# UBX_NORA_B1_SCHEM_0001_NORA_B1_Module.net
KiCad netlist of a schematic drawn in Altium Designer
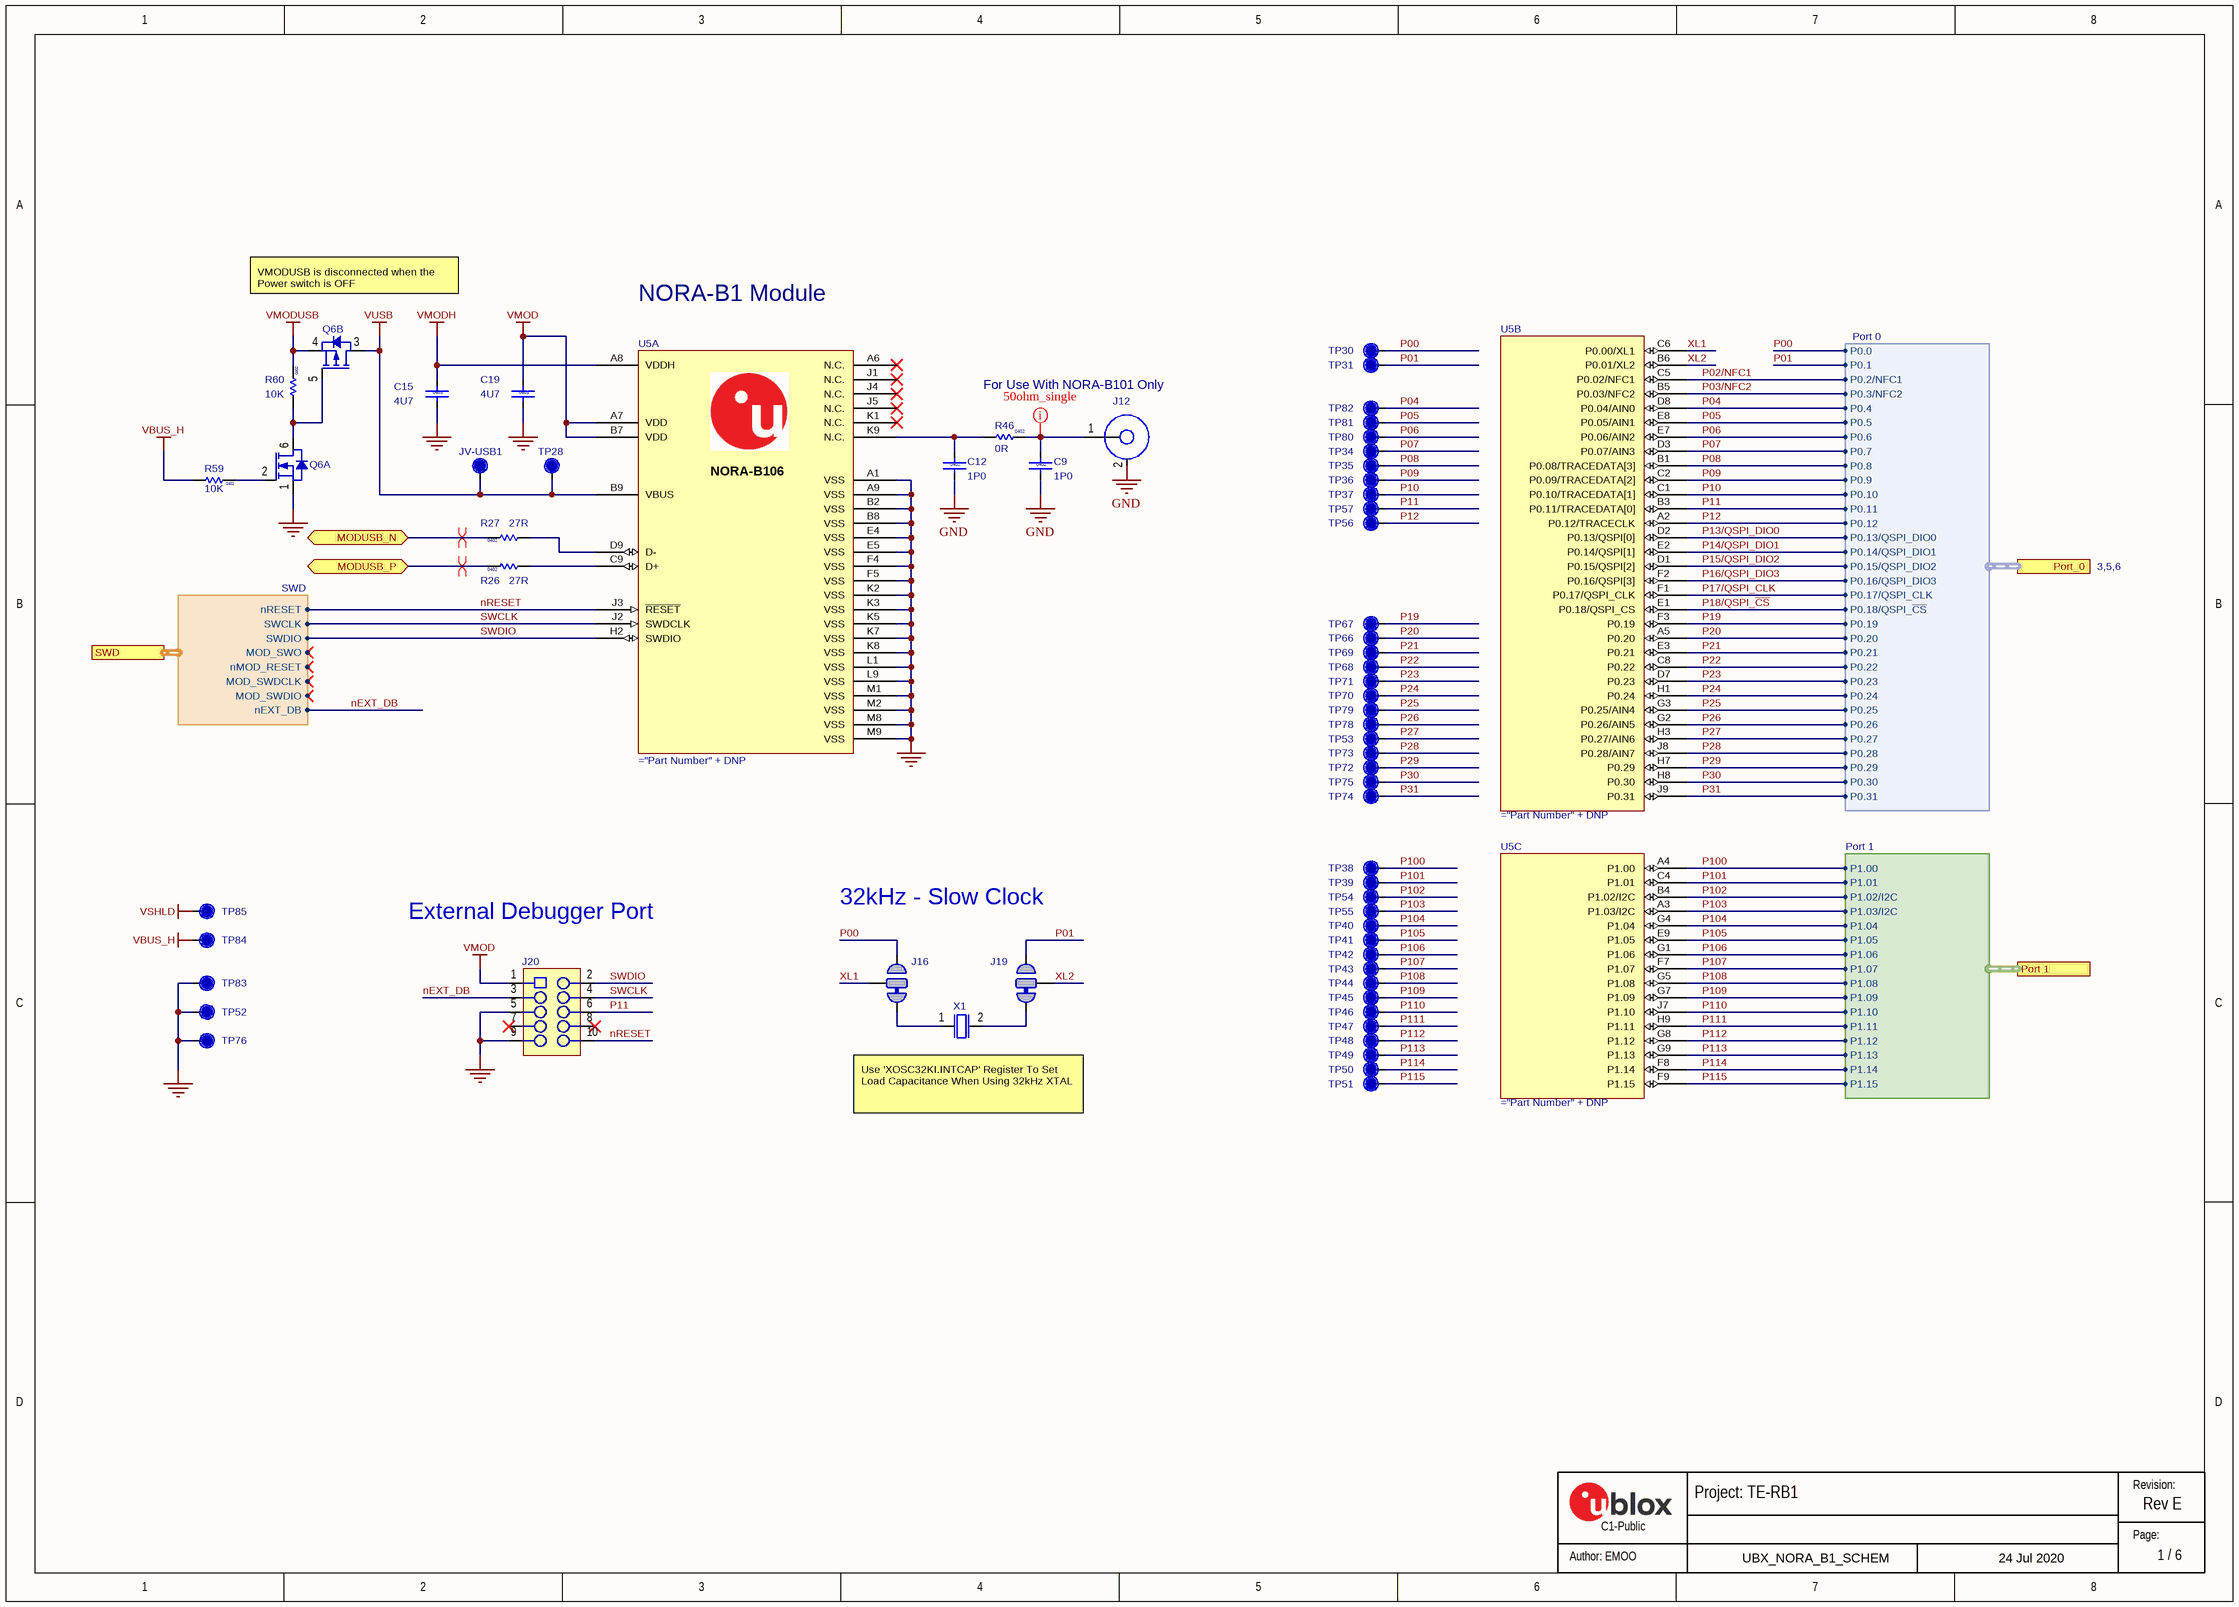
[diagram p0: UBX_NORA_B1_SCHEM_0001_NORA_B1_Module.SchDoc]

(export (version "E")
  (design (tool "Eeschema 10.0.6"))
  (components
    (comp (ref "C9")
      (value "1P0")
      (footprint "Cap 0402 HD")
      (description "CAP CER C0G 0402 1P0 +/-0.1P 50V")
      (fields
        (field (name "SIZE") "0402")
        (field (name "PART NUMBER") "UBXH01-0009002")
        (field (name "TOLERANCE") "+/-0.1P")
        (field (name "EDITOR") "massimo.vlacci")
        (field (name "RELEASED BY") "sandro.sestan")
      )
      (libsource (lib "UBX_Parts_DB_Lib") (part "Cap Chip"))
    )
    (comp (ref "C12")
      (value "1P0")
      (footprint "Cap 0402 HD")
      (description "CAP CER C0G 0402 1P0 +/-0.1P 50V")
      (fields
        (field (name "SIZE") "0402")
        (field (name "PART NUMBER") "UBXH01-0009002")
        (field (name "TOLERANCE") "+/-0.1P")
        (field (name "EDITOR") "massimo.vlacci")
        (field (name "RELEASED BY") "sandro.sestan")
      )
      (libsource (lib "UBX_Parts_DB_Lib") (part "Cap Chip"))
    )
    (comp (ref "C15")
      (value "4U7")
      (footprint "CAP 0603 HD")
      (description "CAP CER X5R 0603 4U7 10% 6.3V")
      (fields
        (field (name "SIZE") "0603")
        (field (name "PART NUMBER") "UBXH01-2002003")
        (field (name "TOLERANCE") "10%")
        (field (name "EDITOR") "philippe.largier")
        (field (name "RELEASED BY") "roland.rust")
      )
      (libsource (lib "UBX_Parts_DB_Lib") (part "Cap Chip"))
    )
    (comp (ref "C19")
      (value "4U7")
      (footprint "CAP 0603 HD")
      (description "CAP CER X5R 0603 4U7 10% 6.3V")
      (fields
        (field (name "SIZE") "0603")
        (field (name "PART NUMBER") "UBXH01-2002003")
        (field (name "TOLERANCE") "10%")
        (field (name "EDITOR") "philippe.largier")
        (field (name "RELEASED BY") "roland.rust")
      )
      (libsource (lib "UBX_Parts_DB_Lib") (part "Cap Chip"))
    )
    (comp (ref "J12")
      (value "UBXH04-0000657")
      (footprint "U.FL_3Pin")
      (description "CONN U.FL STRAIGHT RECEPTACLE")
      (fields
        (field (name "MANUFACTURER") "Hirose")
        (field (name "EDITOR") "cam.nichols")
        (field (name "RELEASED BY") "eric.moog")
      )
      (libsource (lib "UBX_Parts_DB_Lib") (part "CON_Coax_2Pin"))
    )
    (comp (ref "J16")
      (value "UBXH00-0000083")
      (footprint "Solderbridge-Option")
      (description "SOLDERBRIDGE-OPTION")
      (fields (field (name "EDITOR") "aneeb.sohail"))
      (libsource (lib "") (part "Solderbridge-Option_1"))
    )
    (comp (ref "J19")
      (value "UBXH00-0000083")
      (footprint "Solderbridge-Option")
      (description "SOLDERBRIDGE-OPTION")
      (fields (field (name "EDITOR") "aneeb.sohail"))
      (libsource (lib "UBX_Parts_DB_Lib") (part "Solderbridge-Option"))
    )
    (comp (ref "J20")
      (value "UBXH04-0000194")
      (footprint "FTSH-105-01-F-DV-K")
      (description "2-ROW SMD-PCB CONN 50MIL GRID 10 -PIN 0.41MM SQUARE 4.0MM KEYED")
      (fields
        (field (name "MANUFACTURER") "Samtec")
        (field (name "EDITOR") "par.hakansson")
        (field (name "RELEASED BY") "adam.johansson")
      )
      (libsource (lib "UBX_Parts_DB_Lib") (part "CON-10Pin_2Row"))
    )
    (comp (ref "JV-USB1")
      (value "TP")
      (footprint "TP10R_NO_SILK")
      (description "TESTPOINT 1MM CIRCULAR NO SILKSCREEN")
      (fields (field (name "PART NUMBER") "UBXH00-0000096") (field (name "EDITOR") "eric.moog"))
      (libsource (lib "UBX_Parts_DB_Lib") (part "TP_R"))
    )
    (comp (ref "Q6")
      (value "UBXH20-0000084")
      (footprint "SOT-563")
      (description "SMALL SIGNAL COMPLEMENTARY W/ ESD PROTECTION MOSFET SOT-563-6 PACKAGE")
      (fields
        (field (name "MANUFACTURER") "ON Semiconductor")
        (field (name "EDITOR") "pierpaolo.arban")
        (field (name "RELEASED BY") "matej.budin")
      )
      (libsource (lib "UBX_Parts_DB_Lib") (part "MOSFET-N-P_Pair"))
    )
    (comp (ref "R26")
      (value "27R")
      (footprint "RES 0402 HD")
      (description "RES THICK FILM CHIP 0402 27R 5% 100mW")
      (fields
        (field (name "SIZE") "0402")
        (field (name "PART NUMBER") "UBXH18-0008011")
        (field (name "TOLERANCE") "5%")
        (field (name "EDITOR") "roland.rust")
        (field (name "RELEASED BY") "roland.rust")
      )
      (libsource (lib "UBX_Parts_DB_Lib") (part "Res sm"))
    )
    (comp (ref "R27")
      (value "27R")
      (footprint "RES 0402 HD")
      (description "RES THICK FILM CHIP 0402 27R 5% 100mW")
      (fields
        (field (name "SIZE") "0402")
        (field (name "PART NUMBER") "UBXH18-0008011")
        (field (name "TOLERANCE") "5%")
        (field (name "EDITOR") "roland.rust")
        (field (name "RELEASED BY") "roland.rust")
      )
      (libsource (lib "UBX_Parts_DB_Lib") (part "Res sm"))
    )
    (comp (ref "R46")
      (value "0R")
      (footprint "RES 0402 HD")
      (description "RES THICK FILM CHIP 0402 0R 0 100mW")
      (fields
        (field (name "SIZE") "0402")
        (field (name "PART NUMBER") "UBXH18-0003002")
        (field (name "TOLERANCE") "0")
        (field (name "EDITOR") "charlotte.biber")
        (field (name "RELEASED BY") "peter.mueller")
      )
      (libsource (lib "UBX_Parts_DB_Lib") (part "Res sm"))
    )
    (comp (ref "R59")
      (value "10K")
      (footprint "RES 0402 HD")
      (description "RES THICK FILM CHIP 0402 10K 1% 63mW")
      (fields
        (field (name "SIZE") "0402")
        (field (name "PART NUMBER") "UBXH18-0000065")
        (field (name "TOLERANCE") "1%")
        (field (name "EDITOR") "erian.bezhani")
        (field (name "RELEASED BY") "massimo.vlacci")
      )
      (libsource (lib "UBX_Parts_DB_Lib") (part "Res sm"))
    )
    (comp (ref "R60")
      (value "10K")
      (footprint "RES 0402 HD")
      (description "RES THICK FILM CHIP 0402 10K 1% 63mW")
      (fields
        (field (name "SIZE") "0402")
        (field (name "PART NUMBER") "UBXH18-0000065")
        (field (name "TOLERANCE") "1%")
        (field (name "EDITOR") "erian.bezhani")
        (field (name "RELEASED BY") "massimo.vlacci")
      )
      (libsource (lib "UBX_Parts_DB_Lib") (part "Res sm"))
    )
    (comp (ref "TP28")
      (value "TP")
      (footprint "TP10R_NO_SILK")
      (description "TESTPOINT 1MM CIRCULAR NO SILKSCREEN")
      (fields (field (name "PART NUMBER") "UBXH00-0000096") (field (name "EDITOR") "eric.moog"))
      (libsource (lib "UBX_Parts_DB_Lib") (part "TP_R"))
    )
    (comp (ref "TP30")
      (value "TP")
      (footprint "TP10R_NO_SILK")
      (description "TESTPOINT 1MM CIRCULAR NO SILKSCREEN")
      (fields (field (name "PART NUMBER") "UBXH00-0000096") (field (name "EDITOR") "eric.moog"))
      (libsource (lib "UBX_Parts_DB_Lib") (part "TP_R"))
    )
    (comp (ref "TP31")
      (value "TP")
      (footprint "TP10R_NO_SILK")
      (description "TESTPOINT 1MM CIRCULAR NO SILKSCREEN")
      (fields (field (name "PART NUMBER") "UBXH00-0000096") (field (name "EDITOR") "eric.moog"))
      (libsource (lib "UBX_Parts_DB_Lib") (part "TP_R"))
    )
    (comp (ref "TP34")
      (value "TP")
      (footprint "TP10R_NO_SILK")
      (description "TESTPOINT 1MM CIRCULAR NO SILKSCREEN")
      (fields (field (name "PART NUMBER") "UBXH00-0000096") (field (name "EDITOR") "eric.moog"))
      (libsource (lib "UBX_Parts_DB_Lib") (part "TP_R"))
    )
    (comp (ref "TP35")
      (value "TP")
      (footprint "TP10R_NO_SILK")
      (description "TESTPOINT 1MM CIRCULAR NO SILKSCREEN")
      (fields (field (name "PART NUMBER") "UBXH00-0000096") (field (name "EDITOR") "eric.moog"))
      (libsource (lib "UBX_Parts_DB_Lib") (part "TP_R"))
    )
    (comp (ref "TP36")
      (value "TP")
      (footprint "TP10R_NO_SILK")
      (description "TESTPOINT 1MM CIRCULAR NO SILKSCREEN")
      (fields (field (name "PART NUMBER") "UBXH00-0000096") (field (name "EDITOR") "eric.moog"))
      (libsource (lib "UBX_Parts_DB_Lib") (part "TP_R"))
    )
    (comp (ref "TP37")
      (value "TP")
      (footprint "TP10R_NO_SILK")
      (description "TESTPOINT 1MM CIRCULAR NO SILKSCREEN")
      (fields (field (name "PART NUMBER") "UBXH00-0000096") (field (name "EDITOR") "eric.moog"))
      (libsource (lib "UBX_Parts_DB_Lib") (part "TP_R"))
    )
    (comp (ref "TP38")
      (value "TP")
      (footprint "TP10R_NO_SILK")
      (description "TESTPOINT 1MM CIRCULAR NO SILKSCREEN")
      (fields (field (name "PART NUMBER") "UBXH00-0000096") (field (name "EDITOR") "eric.moog"))
      (libsource (lib "UBX_Parts_DB_Lib") (part "TP_R"))
    )
    (comp (ref "TP39")
      (value "TP")
      (footprint "TP10R_NO_SILK")
      (description "TESTPOINT 1MM CIRCULAR NO SILKSCREEN")
      (fields (field (name "PART NUMBER") "UBXH00-0000096") (field (name "EDITOR") "eric.moog"))
      (libsource (lib "UBX_Parts_DB_Lib") (part "TP_R"))
    )
    (comp (ref "TP40")
      (value "TP")
      (footprint "TP10R_NO_SILK")
      (description "TESTPOINT 1MM CIRCULAR NO SILKSCREEN")
      (fields (field (name "PART NUMBER") "UBXH00-0000096") (field (name "EDITOR") "eric.moog"))
      (libsource (lib "UBX_Parts_DB_Lib") (part "TP_R"))
    )
    (comp (ref "TP41")
      (value "TP")
      (footprint "TP10R_NO_SILK")
      (description "TESTPOINT 1MM CIRCULAR NO SILKSCREEN")
      (fields (field (name "PART NUMBER") "UBXH00-0000096") (field (name "EDITOR") "eric.moog"))
      (libsource (lib "UBX_Parts_DB_Lib") (part "TP_R"))
    )
    (comp (ref "TP42")
      (value "TP")
      (footprint "TP10R_NO_SILK")
      (description "TESTPOINT 1MM CIRCULAR NO SILKSCREEN")
      (fields (field (name "PART NUMBER") "UBXH00-0000096") (field (name "EDITOR") "eric.moog"))
      (libsource (lib "UBX_Parts_DB_Lib") (part "TP_R"))
    )
    (comp (ref "TP43")
      (value "TP")
      (footprint "TP10R_NO_SILK")
      (description "TESTPOINT 1MM CIRCULAR NO SILKSCREEN")
      (fields (field (name "PART NUMBER") "UBXH00-0000096") (field (name "EDITOR") "eric.moog"))
      (libsource (lib "UBX_Parts_DB_Lib") (part "TP_R"))
    )
    (comp (ref "TP44")
      (value "TP")
      (footprint "TP10R_NO_SILK")
      (description "TESTPOINT 1MM CIRCULAR NO SILKSCREEN")
      (fields (field (name "PART NUMBER") "UBXH00-0000096") (field (name "EDITOR") "eric.moog"))
      (libsource (lib "UBX_Parts_DB_Lib") (part "TP_R"))
    )
    (comp (ref "TP45")
      (value "TP")
      (footprint "TP10R_NO_SILK")
      (description "TESTPOINT 1MM CIRCULAR NO SILKSCREEN")
      (fields (field (name "PART NUMBER") "UBXH00-0000096") (field (name "EDITOR") "eric.moog"))
      (libsource (lib "UBX_Parts_DB_Lib") (part "TP_R"))
    )
    (comp (ref "TP46")
      (value "TP")
      (footprint "TP10R_NO_SILK")
      (description "TESTPOINT 1MM CIRCULAR NO SILKSCREEN")
      (fields (field (name "PART NUMBER") "UBXH00-0000096") (field (name "EDITOR") "eric.moog"))
      (libsource (lib "UBX_Parts_DB_Lib") (part "TP_R"))
    )
    (comp (ref "TP47")
      (value "TP")
      (footprint "TP10R_NO_SILK")
      (description "TESTPOINT 1MM CIRCULAR NO SILKSCREEN")
      (fields (field (name "PART NUMBER") "UBXH00-0000096") (field (name "EDITOR") "eric.moog"))
      (libsource (lib "UBX_Parts_DB_Lib") (part "TP_R"))
    )
    (comp (ref "TP48")
      (value "TP")
      (footprint "TP10R_NO_SILK")
      (description "TESTPOINT 1MM CIRCULAR NO SILKSCREEN")
      (fields (field (name "PART NUMBER") "UBXH00-0000096") (field (name "EDITOR") "eric.moog"))
      (libsource (lib "UBX_Parts_DB_Lib") (part "TP_R"))
    )
    (comp (ref "TP49")
      (value "TP")
      (footprint "TP10R_NO_SILK")
      (description "TESTPOINT 1MM CIRCULAR NO SILKSCREEN")
      (fields (field (name "PART NUMBER") "UBXH00-0000096") (field (name "EDITOR") "eric.moog"))
      (libsource (lib "UBX_Parts_DB_Lib") (part "TP_R"))
    )
    (comp (ref "TP50")
      (value "TP")
      (footprint "TP10R_NO_SILK")
      (description "TESTPOINT 1MM CIRCULAR NO SILKSCREEN")
      (fields (field (name "PART NUMBER") "UBXH00-0000096") (field (name "EDITOR") "eric.moog"))
      (libsource (lib "UBX_Parts_DB_Lib") (part "TP_R"))
    )
    (comp (ref "TP51")
      (value "TP")
      (footprint "TP10R_NO_SILK")
      (description "TESTPOINT 1MM CIRCULAR NO SILKSCREEN")
      (fields (field (name "PART NUMBER") "UBXH00-0000096") (field (name "EDITOR") "eric.moog"))
      (libsource (lib "UBX_Parts_DB_Lib") (part "TP_R"))
    )
    (comp (ref "TP52")
      (value "TP")
      (footprint "TP10R_NO_SILK")
      (description "TESTPOINT 1MM CIRCULAR NO SILKSCREEN")
      (fields (field (name "PART NUMBER") "UBXH00-0000096") (field (name "EDITOR") "eric.moog"))
      (libsource (lib "UBX_Parts_DB_Lib") (part "TP_R"))
    )
    (comp (ref "TP53")
      (value "TP")
      (footprint "TP10R_NO_SILK")
      (description "TESTPOINT 1MM CIRCULAR NO SILKSCREEN")
      (fields (field (name "PART NUMBER") "UBXH00-0000096") (field (name "EDITOR") "eric.moog"))
      (libsource (lib "UBX_Parts_DB_Lib") (part "TP_R"))
    )
    (comp (ref "TP54")
      (value "TP")
      (footprint "TP10R_NO_SILK")
      (description "TESTPOINT 1MM CIRCULAR NO SILKSCREEN")
      (fields (field (name "PART NUMBER") "UBXH00-0000096") (field (name "EDITOR") "eric.moog"))
      (libsource (lib "UBX_Parts_DB_Lib") (part "TP_R"))
    )
    (comp (ref "TP55")
      (value "TP")
      (footprint "TP10R_NO_SILK")
      (description "TESTPOINT 1MM CIRCULAR NO SILKSCREEN")
      (fields (field (name "PART NUMBER") "UBXH00-0000096") (field (name "EDITOR") "eric.moog"))
      (libsource (lib "UBX_Parts_DB_Lib") (part "TP_R"))
    )
    (comp (ref "TP56")
      (value "TP")
      (footprint "TP10R_NO_SILK")
      (description "TESTPOINT 1MM CIRCULAR NO SILKSCREEN")
      (fields (field (name "PART NUMBER") "UBXH00-0000096") (field (name "EDITOR") "eric.moog"))
      (libsource (lib "UBX_Parts_DB_Lib") (part "TP_R"))
    )
    (comp (ref "TP57")
      (value "TP")
      (footprint "TP10R_NO_SILK")
      (description "TESTPOINT 1MM CIRCULAR NO SILKSCREEN")
      (fields (field (name "PART NUMBER") "UBXH00-0000096") (field (name "EDITOR") "eric.moog"))
      (libsource (lib "UBX_Parts_DB_Lib") (part "TP_R"))
    )
    (comp (ref "TP66")
      (value "TP")
      (footprint "TP10R_NO_SILK")
      (description "TESTPOINT 1MM CIRCULAR NO SILKSCREEN")
      (fields (field (name "PART NUMBER") "UBXH00-0000096") (field (name "EDITOR") "eric.moog"))
      (libsource (lib "UBX_Parts_DB_Lib") (part "TP_R"))
    )
    (comp (ref "TP67")
      (value "TP")
      (footprint "TP10R_NO_SILK")
      (description "TESTPOINT 1MM CIRCULAR NO SILKSCREEN")
      (fields (field (name "PART NUMBER") "UBXH00-0000096") (field (name "EDITOR") "eric.moog"))
      (libsource (lib "UBX_Parts_DB_Lib") (part "TP_R"))
    )
    (comp (ref "TP68")
      (value "TP")
      (footprint "TP10R_NO_SILK")
      (description "TESTPOINT 1MM CIRCULAR NO SILKSCREEN")
      (fields (field (name "PART NUMBER") "UBXH00-0000096") (field (name "EDITOR") "eric.moog"))
      (libsource (lib "UBX_Parts_DB_Lib") (part "TP_R"))
    )
    (comp (ref "TP69")
      (value "TP")
      (footprint "TP10R_NO_SILK")
      (description "TESTPOINT 1MM CIRCULAR NO SILKSCREEN")
      (fields (field (name "PART NUMBER") "UBXH00-0000096") (field (name "EDITOR") "eric.moog"))
      (libsource (lib "UBX_Parts_DB_Lib") (part "TP_R"))
    )
    (comp (ref "TP70")
      (value "TP")
      (footprint "TP10R_NO_SILK")
      (description "TESTPOINT 1MM CIRCULAR NO SILKSCREEN")
      (fields (field (name "PART NUMBER") "UBXH00-0000096") (field (name "EDITOR") "eric.moog"))
      (libsource (lib "UBX_Parts_DB_Lib") (part "TP_R"))
    )
    (comp (ref "TP71")
      (value "TP")
      (footprint "TP10R_NO_SILK")
      (description "TESTPOINT 1MM CIRCULAR NO SILKSCREEN")
      (fields (field (name "PART NUMBER") "UBXH00-0000096") (field (name "EDITOR") "eric.moog"))
      (libsource (lib "UBX_Parts_DB_Lib") (part "TP_R"))
    )
    (comp (ref "TP72")
      (value "TP")
      (footprint "TP10R_NO_SILK")
      (description "TESTPOINT 1MM CIRCULAR NO SILKSCREEN")
      (fields (field (name "PART NUMBER") "UBXH00-0000096") (field (name "EDITOR") "eric.moog"))
      (libsource (lib "UBX_Parts_DB_Lib") (part "TP_R"))
    )
    (comp (ref "TP73")
      (value "TP")
      (footprint "TP10R_NO_SILK")
      (description "TESTPOINT 1MM CIRCULAR NO SILKSCREEN")
      (fields (field (name "PART NUMBER") "UBXH00-0000096") (field (name "EDITOR") "eric.moog"))
      (libsource (lib "UBX_Parts_DB_Lib") (part "TP_R"))
    )
    (comp (ref "TP74")
      (value "TP")
      (footprint "TP10R_NO_SILK")
      (description "TESTPOINT 1MM CIRCULAR NO SILKSCREEN")
      (fields (field (name "PART NUMBER") "UBXH00-0000096") (field (name "EDITOR") "eric.moog"))
      (libsource (lib "UBX_Parts_DB_Lib") (part "TP_R"))
    )
    (comp (ref "TP75")
      (value "TP")
      (footprint "TP10R_NO_SILK")
      (description "TESTPOINT 1MM CIRCULAR NO SILKSCREEN")
      (fields (field (name "PART NUMBER") "UBXH00-0000096") (field (name "EDITOR") "eric.moog"))
      (libsource (lib "UBX_Parts_DB_Lib") (part "TP_R"))
    )
    (comp (ref "TP76")
      (value "TP")
      (footprint "TP10R_NO_SILK")
      (description "TESTPOINT 1MM CIRCULAR NO SILKSCREEN")
      (fields (field (name "PART NUMBER") "UBXH00-0000096") (field (name "EDITOR") "eric.moog"))
      (libsource (lib "UBX_Parts_DB_Lib") (part "TP_R"))
    )
    (comp (ref "TP78")
      (value "TP")
      (footprint "TP10R_NO_SILK")
      (description "TESTPOINT 1MM CIRCULAR NO SILKSCREEN")
      (fields (field (name "PART NUMBER") "UBXH00-0000096") (field (name "EDITOR") "eric.moog"))
      (libsource (lib "UBX_Parts_DB_Lib") (part "TP_R"))
    )
    (comp (ref "TP79")
      (value "TP")
      (footprint "TP10R_NO_SILK")
      (description "TESTPOINT 1MM CIRCULAR NO SILKSCREEN")
      (fields (field (name "PART NUMBER") "UBXH00-0000096") (field (name "EDITOR") "eric.moog"))
      (libsource (lib "UBX_Parts_DB_Lib") (part "TP_R"))
    )
    (comp (ref "TP80")
      (value "TP")
      (footprint "TP10R_NO_SILK")
      (description "TESTPOINT 1MM CIRCULAR NO SILKSCREEN")
      (fields (field (name "PART NUMBER") "UBXH00-0000096") (field (name "EDITOR") "eric.moog"))
      (libsource (lib "UBX_Parts_DB_Lib") (part "TP_R"))
    )
    (comp (ref "TP81")
      (value "TP")
      (footprint "TP10R_NO_SILK")
      (description "TESTPOINT 1MM CIRCULAR NO SILKSCREEN")
      (fields (field (name "PART NUMBER") "UBXH00-0000096") (field (name "EDITOR") "eric.moog"))
      (libsource (lib "UBX_Parts_DB_Lib") (part "TP_R"))
    )
    (comp (ref "TP82")
      (value "TP")
      (footprint "TP10R_NO_SILK")
      (description "TESTPOINT 1MM CIRCULAR NO SILKSCREEN")
      (fields (field (name "PART NUMBER") "UBXH00-0000096") (field (name "EDITOR") "eric.moog"))
      (libsource (lib "UBX_Parts_DB_Lib") (part "TP_R"))
    )
    (comp (ref "TP83")
      (value "TP")
      (footprint "TP10R_NO_SILK")
      (description "TESTPOINT 1MM CIRCULAR NO SILKSCREEN")
      (fields (field (name "PART NUMBER") "UBXH00-0000096") (field (name "EDITOR") "eric.moog"))
      (libsource (lib "UBX_Parts_DB_Lib") (part "TP_R"))
    )
    (comp (ref "TP84")
      (value "TP")
      (footprint "TP10R_NO_SILK")
      (description "TESTPOINT 1MM CIRCULAR NO SILKSCREEN")
      (fields (field (name "PART NUMBER") "UBXH00-0000096") (field (name "EDITOR") "eric.moog"))
      (libsource (lib "UBX_Parts_DB_Lib") (part "TP_R"))
    )
    (comp (ref "TP85")
      (value "TP")
      (footprint "TP10R_NO_SILK")
      (description "TESTPOINT 1MM CIRCULAR NO SILKSCREEN")
      (fields (field (name "PART NUMBER") "UBXH00-0000096") (field (name "EDITOR") "eric.moog"))
      (libsource (lib "UBX_Parts_DB_Lib") (part "TP_R"))
    )
    (comp (ref "U5")
      (value "UBXH14-0000700")
      (footprint "NORA-B106")
      (description "SHORT RANGE BLE AND 802.15.4 MODULE U-BLOX NORA-B106 5.5V 10mA")
      (fields
        (field (name "MANUFACTURER") "u-blox")
        (field (name "VOLTAGE") "5.5V")
        (field (name "EDITOR") "eric.moog")
      )
      (libsource (lib "UBX_Parts_DB_Lib") (part "NORA-B106"))
    )
    (comp (ref "X1")
      (value "UBXH21-0000123")
      (footprint "XTAL_3215")
      (description "CRYSTAL CL=6PF 3.2 X 1.5 MM 32.768KHZ 20PPM")
      (fields
        (field (name "TOLERANCE") "20PPM")
        (field (name "MANUFACTURER") "ABRACON")
        (field (name "EDITOR") "martin.grasse")
      )
      (libsource (lib "UBX_Parts_DB_Lib") (part "XTAL_2Pin"))
    )
  )
  (nets
    (net (code "5") (name "/MODUSB_N") (class "Default")
      (node (ref "R27") (pin "2") (pinfunction "2_2") (pintype "passive"))
    )
    (net (code "6") (name "/MODUSB_P") (class "Default")
      (node (ref "R26") (pin "2") (pinfunction "2_2") (pintype "passive"))
    )
    (net (code "7") (name "/P00") (class "Default")
      (node (ref "J16") (pin "3") (pinfunction "3_3") (pintype "passive"))
      (node (ref "TP30") (pin "1") (pintype "passive"))
    )
    (net (code "8") (name "/P01") (class "Default")
      (node (ref "J19") (pin "3") (pinfunction "3_3") (pintype "passive"))
      (node (ref "TP31") (pin "1") (pintype "passive"))
    )
    (net (code "9") (name "/P02{slash}NFC1") (class "Default")
      (node (ref "U5") (pin "C5") (pinfunction "P0.02/NFC1_C5") (pintype "bidirectional"))
    )
    (net (code "10") (name "/P03{slash}NFC2") (class "Default")
      (node (ref "U5") (pin "B5") (pinfunction "P0.03/NFC2_B5") (pintype "bidirectional"))
    )
    (net (code "11") (name "/P04") (class "Default")
      (node (ref "TP82") (pin "1") (pintype "passive"))
      (node (ref "U5") (pin "D8") (pinfunction "P0.04/AIN0_D8") (pintype "bidirectional"))
    )
    (net (code "12") (name "/P05") (class "Default")
      (node (ref "TP81") (pin "1") (pintype "passive"))
      (node (ref "U5") (pin "E8") (pinfunction "P0.05/AIN1_E8") (pintype "bidirectional"))
    )
    (net (code "13") (name "/P06") (class "Default")
      (node (ref "TP80") (pin "1") (pintype "passive"))
      (node (ref "U5") (pin "E7") (pinfunction "P0.06/AIN2_E7") (pintype "bidirectional"))
    )
    (net (code "14") (name "/P07") (class "Default")
      (node (ref "TP34") (pin "1") (pintype "passive"))
      (node (ref "U5") (pin "D3") (pinfunction "P0.07/AIN3_D3") (pintype "bidirectional"))
    )
    (net (code "15") (name "/P08") (class "Default")
      (node (ref "TP35") (pin "1") (pintype "passive"))
      (node (ref "U5") (pin "B1") (pinfunction "P0.08/TRACEDATA[3]_B1") (pintype "bidirectional"))
    )
    (net (code "16") (name "/P09") (class "Default")
      (node (ref "TP36") (pin "1") (pintype "passive"))
      (node (ref "U5") (pin "C2") (pinfunction "P0.09/TRACEDATA[2]_C2") (pintype "bidirectional"))
    )
    (net (code "17") (name "/P10") (class "Default")
      (node (ref "TP37") (pin "1") (pintype "passive"))
      (node (ref "U5") (pin "C1") (pinfunction "P0.10/TRACEDATA[1]_C1") (pintype "bidirectional"))
    )
    (net (code "18") (name "/P11") (class "Default")
      (node (ref "J20") (pin "6") (pintype "passive"))
      (node (ref "TP57") (pin "1") (pintype "passive"))
      (node (ref "U5") (pin "B3") (pinfunction "P0.11/TRACEDATA[0]_B3") (pintype "bidirectional"))
    )
    (net (code "19") (name "/P12") (class "Default")
      (node (ref "TP56") (pin "1") (pintype "passive"))
      (node (ref "U5") (pin "A2") (pinfunction "P0.12/TRACECLK_A2") (pintype "bidirectional"))
    )
    (net (code "20") (name "/P13{slash}QSPI_DIO0") (class "Default")
      (node (ref "U5") (pin "D2") (pinfunction "P0.13/QSPI[0]_D2") (pintype "bidirectional"))
    )
    (net (code "21") (name "/P14{slash}QSPI_DIO1") (class "Default")
      (node (ref "U5") (pin "E2") (pinfunction "P0.14/QSPI[1]_E2") (pintype "bidirectional"))
    )
    (net (code "22") (name "/P15{slash}QSPI_DIO2") (class "Default")
      (node (ref "U5") (pin "D1") (pinfunction "P0.15/QSPI[2]_D1") (pintype "bidirectional"))
    )
    (net (code "23") (name "/P16{slash}QSPI_DIO3") (class "Default")
      (node (ref "U5") (pin "F2") (pinfunction "P0.16/QSPI[3]_F2") (pintype "bidirectional"))
    )
    (net (code "24") (name "/P17{slash}QSPI_CLK") (class "Default")
      (node (ref "U5") (pin "F1") (pinfunction "P0.17/QSPI_CLK_F1") (pintype "bidirectional"))
    )
    (net (code "25") (name "/P18{slash}QSPI_~{CS}") (class "Default")
      (node (ref "U5") (pin "E1") (pinfunction "P0.18/QSPI_CS_E1") (pintype "bidirectional"))
    )
    (net (code "26") (name "/P19") (class "Default")
      (node (ref "TP67") (pin "1") (pintype "passive"))
      (node (ref "U5") (pin "F3") (pinfunction "P0.19_F3") (pintype "bidirectional"))
    )
    (net (code "27") (name "/P20") (class "Default")
      (node (ref "TP66") (pin "1") (pintype "passive"))
      (node (ref "U5") (pin "A5") (pinfunction "P0.20_A5") (pintype "bidirectional"))
    )
    (net (code "28") (name "/P21") (class "Default")
      (node (ref "TP69") (pin "1") (pintype "passive"))
      (node (ref "U5") (pin "E3") (pinfunction "P0.21_E3") (pintype "bidirectional"))
    )
    (net (code "29") (name "/P22") (class "Default")
      (node (ref "TP68") (pin "1") (pintype "passive"))
      (node (ref "U5") (pin "C8") (pinfunction "P0.22_C8") (pintype "bidirectional"))
    )
    (net (code "30") (name "/P23") (class "Default")
      (node (ref "TP71") (pin "1") (pintype "passive"))
      (node (ref "U5") (pin "D7") (pinfunction "P0.23_D7") (pintype "bidirectional"))
    )
    (net (code "31") (name "/P24") (class "Default")
      (node (ref "TP70") (pin "1") (pintype "passive"))
      (node (ref "U5") (pin "H1") (pinfunction "P0.24_H1") (pintype "bidirectional"))
    )
    (net (code "32") (name "/P25") (class "Default")
      (node (ref "TP79") (pin "1") (pintype "passive"))
      (node (ref "U5") (pin "G3") (pinfunction "P0.25/AIN4_G3") (pintype "bidirectional"))
    )
    (net (code "33") (name "/P26") (class "Default")
      (node (ref "TP78") (pin "1") (pintype "passive"))
      (node (ref "U5") (pin "G2") (pinfunction "P0.26/AIN5_G2") (pintype "bidirectional"))
    )
    (net (code "34") (name "/P27") (class "Default")
      (node (ref "TP53") (pin "1") (pintype "passive"))
      (node (ref "U5") (pin "H3") (pinfunction "P0.27/AIN6_H3") (pintype "bidirectional"))
    )
    (net (code "35") (name "/P28") (class "Default")
      (node (ref "TP73") (pin "1") (pintype "passive"))
      (node (ref "U5") (pin "J8") (pinfunction "P0.28/AIN7_J8") (pintype "bidirectional"))
    )
    (net (code "36") (name "/P29") (class "Default")
      (node (ref "TP72") (pin "1") (pintype "passive"))
      (node (ref "U5") (pin "H7") (pinfunction "P0.29_H7") (pintype "bidirectional"))
    )
    (net (code "37") (name "/P30") (class "Default")
      (node (ref "TP75") (pin "1") (pintype "passive"))
      (node (ref "U5") (pin "H8") (pinfunction "P0.30_H8") (pintype "bidirectional"))
    )
    (net (code "38") (name "/P31") (class "Default")
      (node (ref "TP74") (pin "1") (pintype "passive"))
      (node (ref "U5") (pin "J9") (pinfunction "P0.31_J9") (pintype "bidirectional"))
    )
    (net (code "39") (name "/P100") (class "Default")
      (node (ref "TP38") (pin "1") (pintype "passive"))
      (node (ref "U5") (pin "A4") (pinfunction "P1.00_A4") (pintype "bidirectional"))
    )
    (net (code "40") (name "/P101") (class "Default")
      (node (ref "TP39") (pin "1") (pintype "passive"))
      (node (ref "U5") (pin "C4") (pinfunction "P1.01_C4") (pintype "bidirectional"))
    )
    (net (code "41") (name "/P102") (class "Default")
      (node (ref "TP54") (pin "1") (pintype "passive"))
      (node (ref "U5") (pin "B4") (pinfunction "P1.02/I2C_B4") (pintype "bidirectional"))
    )
    (net (code "42") (name "/P103") (class "Default")
      (node (ref "TP55") (pin "1") (pintype "passive"))
      (node (ref "U5") (pin "A3") (pinfunction "P1.03/I2C_A3") (pintype "bidirectional"))
    )
    (net (code "43") (name "/P104") (class "Default")
      (node (ref "TP40") (pin "1") (pintype "passive"))
      (node (ref "U5") (pin "G4") (pinfunction "P1.04_G4") (pintype "bidirectional"))
    )
    (net (code "44") (name "/P105") (class "Default")
      (node (ref "TP41") (pin "1") (pintype "passive"))
      (node (ref "U5") (pin "E9") (pinfunction "P1.05_E9") (pintype "bidirectional"))
    )
    (net (code "45") (name "/P106") (class "Default")
      (node (ref "TP42") (pin "1") (pintype "passive"))
      (node (ref "U5") (pin "G1") (pinfunction "P1.06_G1") (pintype "bidirectional"))
    )
    (net (code "46") (name "/P107") (class "Default")
      (node (ref "TP43") (pin "1") (pintype "passive"))
      (node (ref "U5") (pin "F7") (pinfunction "P1.07_F7") (pintype "bidirectional"))
    )
    (net (code "47") (name "/P108") (class "Default")
      (node (ref "TP44") (pin "1") (pintype "passive"))
      (node (ref "U5") (pin "G5") (pinfunction "P1.08_G5") (pintype "bidirectional"))
    )
    (net (code "48") (name "/P109") (class "Default")
      (node (ref "TP45") (pin "1") (pintype "passive"))
      (node (ref "U5") (pin "G7") (pinfunction "P1.09_G7") (pintype "bidirectional"))
    )
    (net (code "49") (name "/P110") (class "Default")
      (node (ref "TP46") (pin "1") (pintype "passive"))
      (node (ref "U5") (pin "J7") (pinfunction "P1.10_J7") (pintype "bidirectional"))
    )
    (net (code "50") (name "/P111") (class "Default")
      (node (ref "TP47") (pin "1") (pintype "passive"))
      (node (ref "U5") (pin "H9") (pinfunction "P1.11_H9") (pintype "bidirectional"))
    )
    (net (code "51") (name "/P112") (class "Default")
      (node (ref "TP48") (pin "1") (pintype "passive"))
      (node (ref "U5") (pin "G8") (pinfunction "P1.12_G8") (pintype "bidirectional"))
    )
    (net (code "52") (name "/P113") (class "Default")
      (node (ref "TP49") (pin "1") (pintype "passive"))
      (node (ref "U5") (pin "G9") (pinfunction "P1.13_G9") (pintype "bidirectional"))
    )
    (net (code "53") (name "/P114") (class "Default")
      (node (ref "TP50") (pin "1") (pintype "passive"))
      (node (ref "U5") (pin "F8") (pinfunction "P1.14_F8") (pintype "bidirectional"))
    )
    (net (code "54") (name "/P115") (class "Default")
      (node (ref "TP51") (pin "1") (pintype "passive"))
      (node (ref "U5") (pin "F9") (pinfunction "P1.15_F9") (pintype "bidirectional"))
    )
    (net (code "55") (name "/SWCLK") (class "Default")
      (node (ref "J20") (pin "4") (pintype "passive"))
      (node (ref "U5") (pin "J2") (pinfunction "SWDCLK_J2") (pintype "input"))
    )
    (net (code "56") (name "/SWDIO") (class "Default")
      (node (ref "J20") (pin "2") (pintype "passive"))
      (node (ref "U5") (pin "H2") (pinfunction "SWDIO_H2") (pintype "bidirectional"))
    )
    (net (code "57") (name "/XL1") (class "Default")
      (node (ref "J16") (pin "2") (pinfunction "2_2") (pintype "passive"))
      (node (ref "U5") (pin "C6") (pinfunction "P0.00/XL1_C6") (pintype "bidirectional"))
    )
    (net (code "58") (name "/XL2") (class "Default")
      (node (ref "J19") (pin "2") (pinfunction "2_2") (pintype "passive"))
      (node (ref "U5") (pin "B6") (pinfunction "P0.01/XL2_B6") (pintype "bidirectional"))
    )
    (net (code "59") (name "/nEXT_DB") (class "Default") (node (ref "J20") (pin "3") (pintype "passive")))
    (net (code "60") (name "/nRESET") (class "Default")
      (node (ref "J20") (pin "10") (pintype "passive"))
      (node (ref "U5") (pin "J3") (pinfunction "~{RESET}_J3") (pintype "input"))
    )
    (net (code "64") (name "GND") (class "Default")
      (node (ref "C12") (pin "2") (pinfunction "2_2") (pintype "passive"))
      (node (ref "C15") (pin "2") (pinfunction "2_2") (pintype "passive"))
      (node (ref "C19") (pin "2") (pinfunction "2_2") (pintype "passive"))
      (node (ref "C9") (pin "2") (pinfunction "2_2") (pintype "passive"))
      (node (ref "J12") (pin "2") (pinfunction "2_2") (pintype "power_in"))
      (node (ref "J20") (pin "5") (pintype "passive"))
      (node (ref "J20") (pin "9") (pintype "passive"))
      (node (ref "Q6") (pin "1") (pinfunction "S1_1") (pintype "passive"))
      (node (ref "TP52") (pin "1") (pintype "passive"))
      (node (ref "TP76") (pin "1") (pintype "passive"))
      (node (ref "TP83") (pin "1") (pintype "passive"))
      (node (ref "U5") (pin "A1") (pinfunction "VSS_A1") (pintype "power_in"))
      (node (ref "U5") (pin "A9") (pinfunction "VSS_A9") (pintype "power_in"))
      (node (ref "U5") (pin "B2") (pinfunction "VSS_B2") (pintype "power_in"))
      (node (ref "U5") (pin "B8") (pinfunction "VSS_B8") (pintype "power_in"))
      (node (ref "U5") (pin "E4") (pinfunction "VSS_E4") (pintype "power_in"))
      (node (ref "U5") (pin "E5") (pinfunction "VSS_E5") (pintype "power_in"))
      (node (ref "U5") (pin "F4") (pinfunction "VSS_F4") (pintype "power_in"))
      (node (ref "U5") (pin "F5") (pinfunction "VSS_F5") (pintype "power_in"))
      (node (ref "U5") (pin "K2") (pinfunction "VSS_K2") (pintype "power_in"))
      (node (ref "U5") (pin "K3") (pinfunction "VSS_K3") (pintype "power_in"))
      (node (ref "U5") (pin "K5") (pinfunction "VSS_K5") (pintype "power_in"))
      (node (ref "U5") (pin "K7") (pinfunction "VSS_K7") (pintype "power_in"))
      (node (ref "U5") (pin "K8") (pinfunction "VSS_K8") (pintype "power_in"))
      (node (ref "U5") (pin "L1") (pinfunction "VSS_L1") (pintype "power_in"))
      (node (ref "U5") (pin "L9") (pinfunction "VSS_L9") (pintype "power_in"))
      (node (ref "U5") (pin "M1") (pinfunction "VSS_M1") (pintype "power_in"))
      (node (ref "U5") (pin "M2") (pinfunction "VSS_M2") (pintype "power_in"))
      (node (ref "U5") (pin "M8") (pinfunction "VSS_M8") (pintype "power_in"))
      (node (ref "U5") (pin "M9") (pinfunction "VSS_M9") (pintype "power_in"))
    )
    (net (code "65") (name "Net-(C12-Pad1)") (class "Default")
      (node (ref "C12") (pin "1") (pinfunction "1_1") (pintype "passive"))
      (node (ref "R46") (pin "1") (pinfunction "1_1") (pintype "passive"))
      (node (ref "U5") (pin "K9") (pinfunction "N.C._K9") (pintype "tri_state"))
    )
    (net (code "66") (name "Net-(J12-ANT)") (class "Default")
      (node (ref "C9") (pin "1") (pinfunction "1_1") (pintype "passive"))
      (node (ref "J12") (pin "1") (pinfunction "ANT_1") (pintype "passive"))
      (node (ref "R46") (pin "2") (pinfunction "2_2") (pintype "passive"))
    )
    (net (code "67") (name "Net-(J16-Pad1)") (class "Default")
      (node (ref "J16") (pin "1") (pinfunction "1_1") (pintype "passive"))
      (node (ref "X1") (pin "1") (pintype "passive"))
    )
    (net (code "68") (name "Net-(J19-Pad1)") (class "Default")
      (node (ref "J19") (pin "1") (pinfunction "1_1") (pintype "passive"))
      (node (ref "X1") (pin "2") (pintype "passive"))
    )
    (net (code "69") (name "Net-(Q6A-D1)") (class "Default")
      (node (ref "Q6") (pin "5") (pinfunction "G2_5") (pintype "passive"))
      (node (ref "Q6") (pin "6") (pinfunction "D1_6") (pintype "passive"))
      (node (ref "R60") (pin "1") (pinfunction "1_1") (pintype "passive"))
    )
    (net (code "70") (name "Net-(Q6A-G1)") (class "Default")
      (node (ref "Q6") (pin "2") (pinfunction "G1_2") (pintype "passive"))
      (node (ref "R59") (pin "2") (pinfunction "2_2") (pintype "passive"))
    )
    (net (code "71") (name "Net-(U5A-D+)") (class "Default")
      (node (ref "R26") (pin "1") (pinfunction "1_1") (pintype "passive"))
      (node (ref "U5") (pin "C9") (pinfunction "D+_C9") (pintype "bidirectional"))
    )
    (net (code "72") (name "Net-(U5A-D-)") (class "Default")
      (node (ref "R27") (pin "1") (pinfunction "1_1") (pintype "passive"))
      (node (ref "U5") (pin "D9") (pinfunction "D-_D9") (pintype "bidirectional"))
    )
    (net (code "73") (name "VBUS_H") (class "Default")
      (node (ref "R59") (pin "1") (pinfunction "1_1") (pintype "passive"))
      (node (ref "TP84") (pin "1") (pintype "passive"))
    )
    (net (code "74") (name "VMOD") (class "Default")
      (node (ref "C19") (pin "1") (pinfunction "1_1") (pintype "passive"))
      (node (ref "J20") (pin "1") (pintype "passive"))
      (node (ref "U5") (pin "A7") (pinfunction "VDD_A7") (pintype "power_in"))
      (node (ref "U5") (pin "B7") (pinfunction "VDD_B7") (pintype "power_in"))
    )
    (net (code "75") (name "VMODH") (class "Default")
      (node (ref "C15") (pin "1") (pinfunction "1_1") (pintype "passive"))
      (node (ref "U5") (pin "A8") (pinfunction "VDDH_A8") (pintype "power_in"))
    )
    (net (code "76") (name "VMODUSB") (class "Default")
      (node (ref "Q6") (pin "4") (pinfunction "S2_4") (pintype "passive"))
      (node (ref "R60") (pin "2") (pinfunction "2_2") (pintype "passive"))
    )
    (net (code "77") (name "VSHLD") (class "Default") (node (ref "TP85") (pin "1") (pintype "passive")))
    (net (code "78") (name "VUSB") (class "Default")
      (node (ref "JV-USB1") (pin "1") (pintype "passive"))
      (node (ref "Q6") (pin "3") (pinfunction "D2_3") (pintype "passive"))
      (node (ref "TP28") (pin "1") (pintype "passive"))
      (node (ref "U5") (pin "B9") (pinfunction "VBUS_B9") (pintype "power_in"))
    )
    (net (code "79") (name "unconnected-(J20-Pad7)") (class "Default")
      (node (ref "J20") (pin "7") (pintype "passive+no_connect"))
    )
    (net (code "80") (name "unconnected-(J20-Pad8)") (class "Default")
      (node (ref "J20") (pin "8") (pintype "passive+no_connect"))
    )
    (net (code "81") (name "unconnected-(U5A-N.C.-PadA6)") (class "Default")
      (node (ref "U5") (pin "A6") (pinfunction "N.C._A6") (pintype "tri_state+no_connect"))
    )
    (net (code "82") (name "unconnected-(U5A-N.C.-PadJ1)") (class "Default")
      (node (ref "U5") (pin "J1") (pinfunction "N.C._J1") (pintype "tri_state+no_connect"))
    )
    (net (code "83") (name "unconnected-(U5A-N.C.-PadJ4)") (class "Default")
      (node (ref "U5") (pin "J4") (pinfunction "N.C._J4") (pintype "tri_state+no_connect"))
    )
    (net (code "84") (name "unconnected-(U5A-N.C.-PadJ5)") (class "Default")
      (node (ref "U5") (pin "J5") (pinfunction "N.C._J5") (pintype "tri_state+no_connect"))
    )
    (net (code "85") (name "unconnected-(U5A-N.C.-PadK1)") (class "Default")
      (node (ref "U5") (pin "K1") (pinfunction "N.C._K1") (pintype "tri_state+no_connect"))
    )
  )
)
